# jumping_ring_ariel.net
KiCad netlist of a schematic drawn in EasyEDA
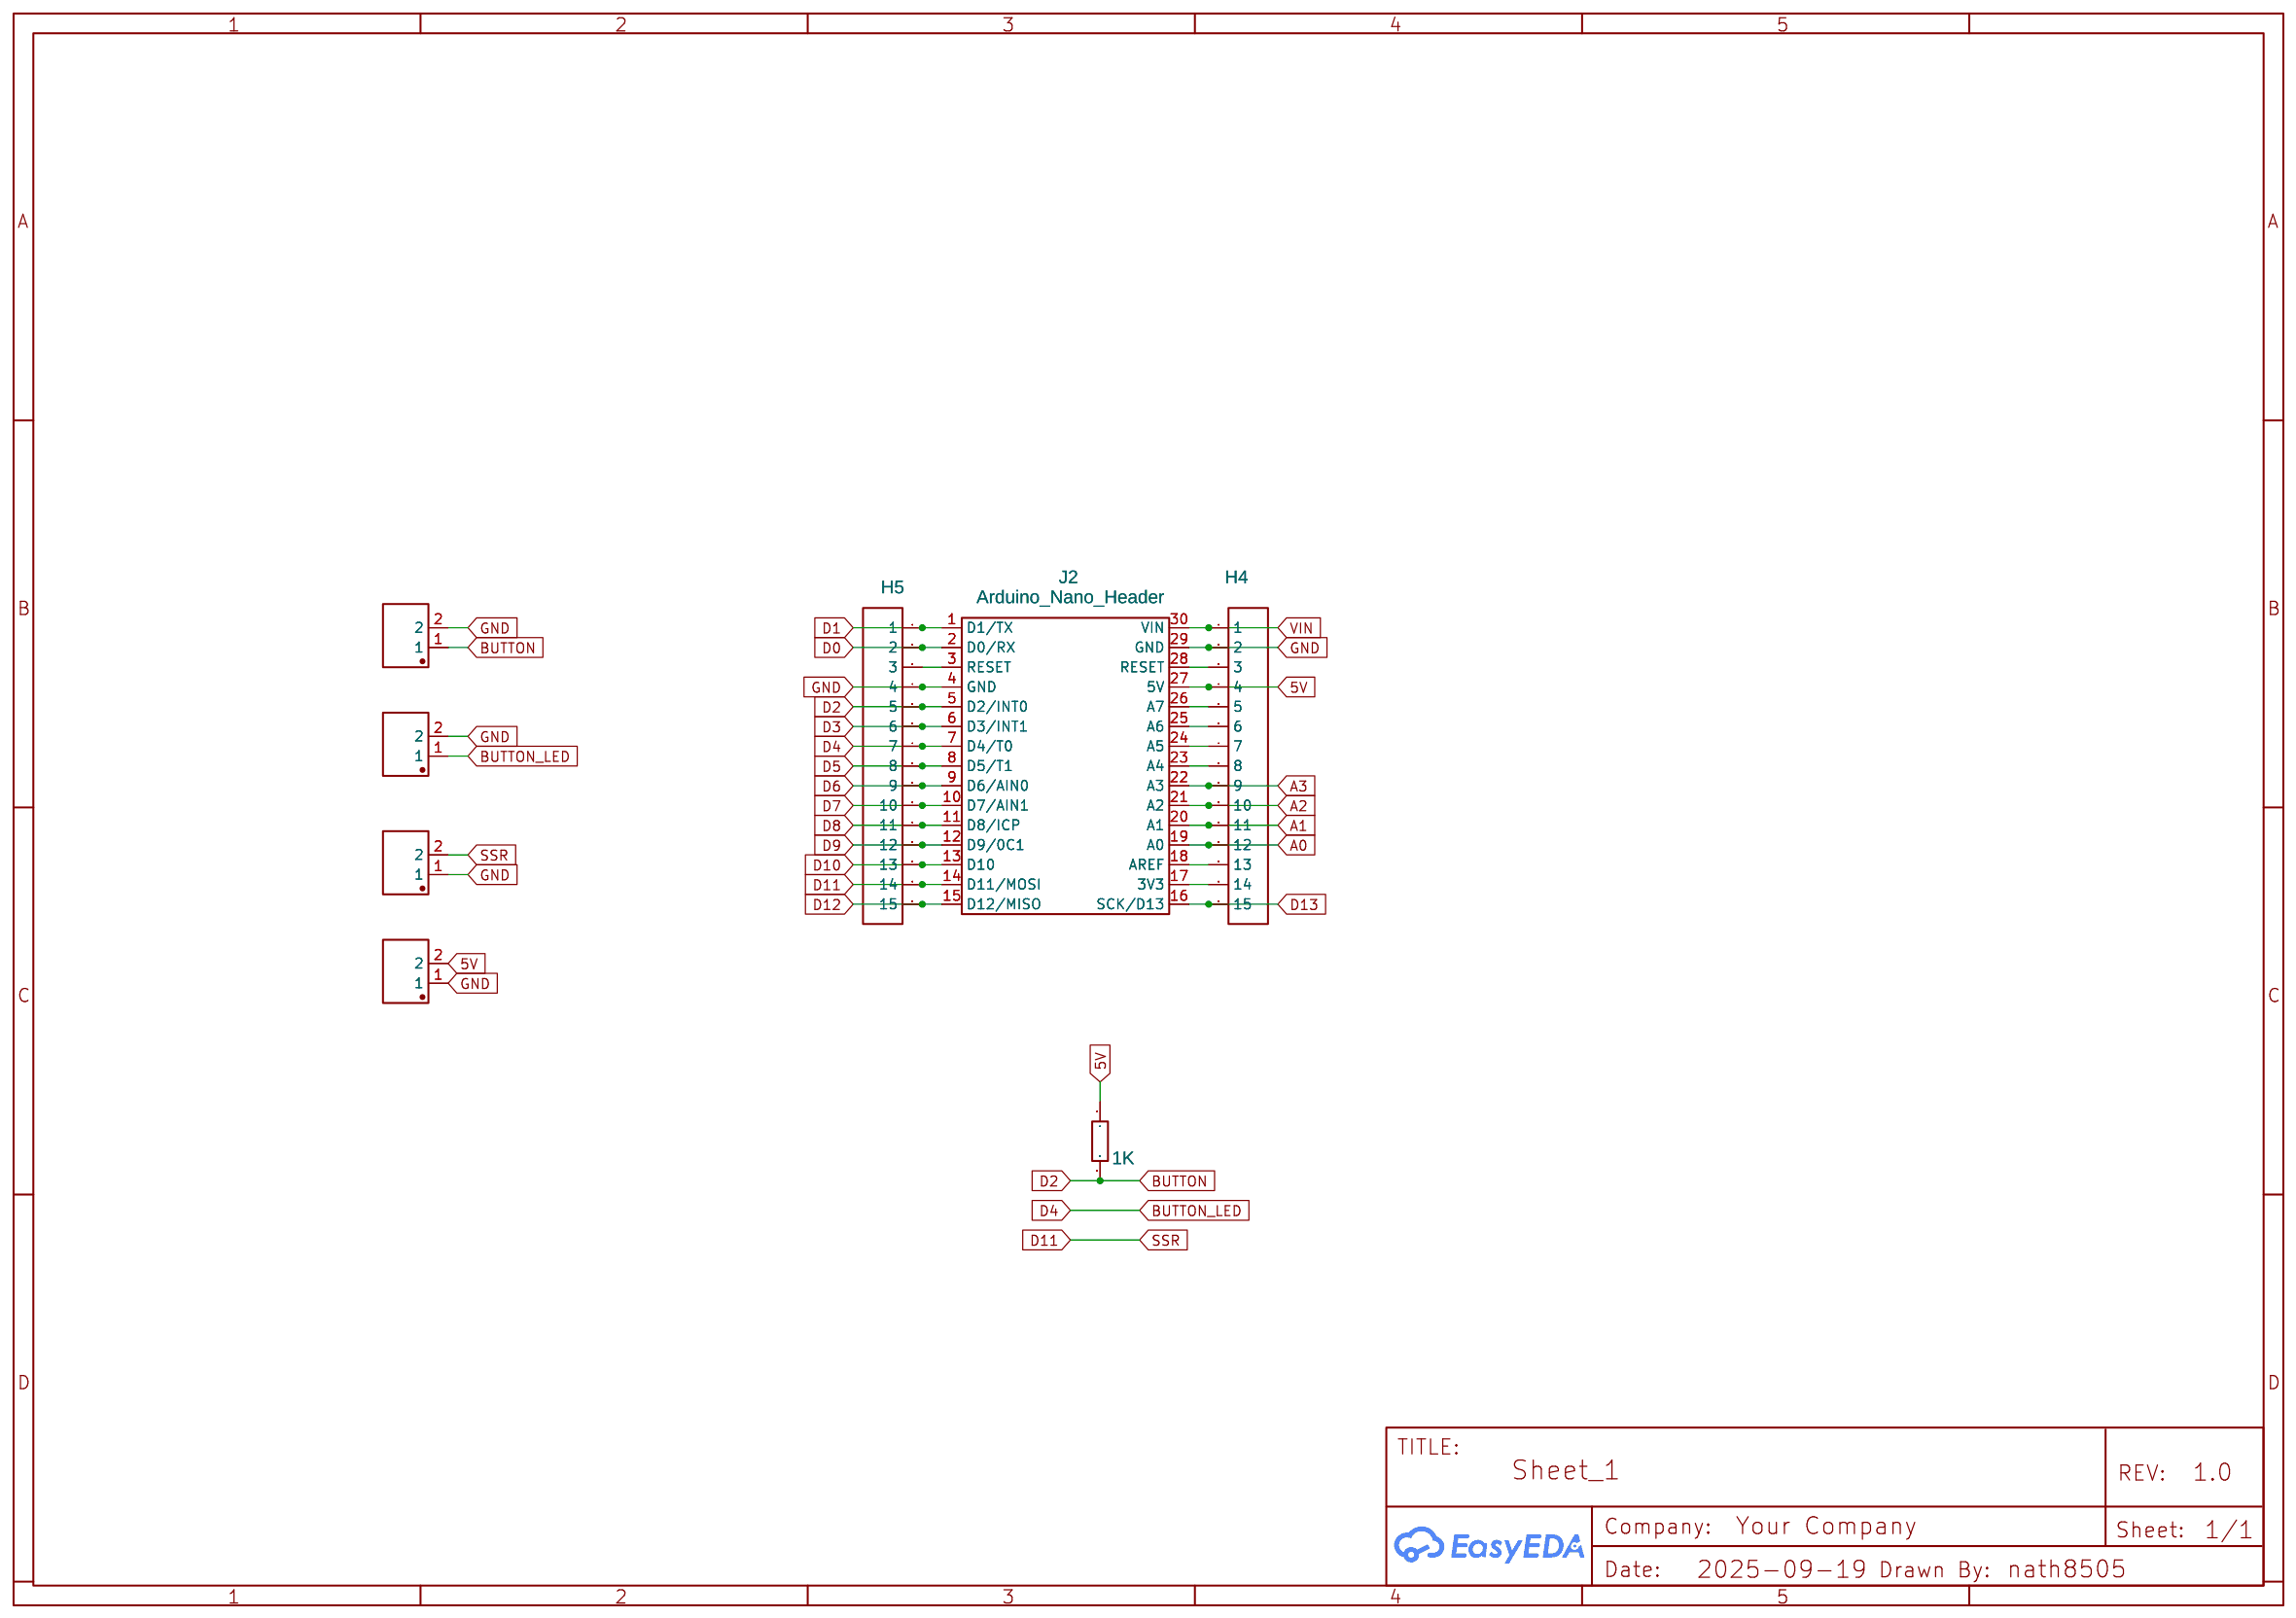
[diagram p0: schematic sheet]

(export (version "E")
  (design (tool "Eeschema 10.0.6"))
  (components
    (comp (ref "D1")
      (value "B-")
      (fields (field (name "Manufacturer Part") "KF2510-2A") (field (name "Manufacturer") "BOOMELE"))
      (libsource (lib "") (part "KF2510-2A"))
    )
    (comp (ref "D2")
      (value "B-")
      (fields (field (name "Manufacturer Part") "KF2510-2A") (field (name "Manufacturer") "BOOMELE"))
      (libsource (lib "") (part "KF2510-2A"))
    )
    (comp (ref "D7")
      (value "B+")
      (fields (field (name "Manufacturer Part") "KF2510-2A") (field (name "Manufacturer") "BOOMELE"))
      (libsource (lib "") (part "KF2510-2A"))
    )
    (comp (ref "D8")
      (value "B-")
      (fields (field (name "Manufacturer Part") "KF2510-2A") (field (name "Manufacturer") "BOOMELE"))
      (libsource (lib "") (part "KF2510-2A"))
    )
    (comp (ref "ERL1")
      (value "1K")
      (fields (field (name "Manufacturer Part") "0603WAF1001T5E") (field (name "Manufacturer") "UniOhm"))
      (libsource (lib "") (part "0603WAF1001T5E"))
    )
    (comp (ref "H4") (value "HDR-F-2.54_1x15") (libsource (lib "") (part "HDR-F-2.54_1x15")))
    (comp (ref "H5") (value "HDR-F-2.54_1x15") (libsource (lib "") (part "HDR-F-2.54_1x15_1")))
    (comp (ref "J2") (value "Arduino_Nano_Header") (libsource (lib "") (part "Arduino_Nano_Header")))
  )
  (nets
    (net (code "1") (name "5V") (class "Default")
      (node (ref "D2") (pin "2") (pinfunction "2_2") (pintype "unspecified"))
      (node (ref "ERL1") (pin "1") (pinfunction "1_1") (pintype "input"))
      (node (ref "H4") (pin "4") (pinfunction "4_4") (pintype "unspecified"))
      (node (ref "J2") (pin "27") (pinfunction "5V_27") (pintype "unspecified"))
    )
    (net (code "2") (name "A0") (class "Default")
      (node (ref "H4") (pin "12") (pinfunction "12_12") (pintype "unspecified"))
      (node (ref "J2") (pin "19") (pinfunction "A0_19") (pintype "unspecified"))
    )
    (net (code "3") (name "A1") (class "Default")
      (node (ref "H4") (pin "11") (pinfunction "11_11") (pintype "unspecified"))
      (node (ref "J2") (pin "20") (pinfunction "A1_20") (pintype "unspecified"))
    )
    (net (code "4") (name "A2") (class "Default")
      (node (ref "H4") (pin "10") (pinfunction "10_10") (pintype "unspecified"))
      (node (ref "J2") (pin "21") (pinfunction "A2_21") (pintype "unspecified"))
    )
    (net (code "5") (name "A3") (class "Default")
      (node (ref "H4") (pin "9") (pinfunction "9_9") (pintype "unspecified"))
      (node (ref "J2") (pin "22") (pinfunction "A3_22") (pintype "unspecified"))
    )
    (net (code "6") (name "BUTTON") (class "Default")
      (node (ref "D7") (pin "1") (pinfunction "1_1") (pintype "unspecified"))
      (node (ref "ERL1") (pin "2") (pinfunction "2_2") (pintype "input"))
      (node (ref "H5") (pin "5") (pinfunction "5_5") (pintype "unspecified"))
      (node (ref "J2") (pin "5") (pinfunction "D2/INT0_5") (pintype "unspecified"))
    )
    (net (code "7") (name "BUTTON_LED") (class "Default")
      (node (ref "D8") (pin "1") (pinfunction "1_1") (pintype "unspecified"))
      (node (ref "H5") (pin "7") (pinfunction "7_7") (pintype "unspecified"))
      (node (ref "J2") (pin "7") (pinfunction "D4/T0_7") (pintype "unspecified"))
    )
    (net (code "8") (name "D0") (class "Default")
      (node (ref "H5") (pin "2") (pinfunction "2_2") (pintype "unspecified"))
      (node (ref "J2") (pin "2") (pinfunction "D0/RX_2") (pintype "unspecified"))
    )
    (net (code "9") (name "D1") (class "Default")
      (node (ref "H5") (pin "1") (pinfunction "1_1") (pintype "unspecified"))
      (node (ref "J2") (pin "1") (pinfunction "D1/TX_1") (pintype "unspecified"))
    )
    (net (code "10") (name "D3") (class "Default")
      (node (ref "H5") (pin "6") (pinfunction "6_6") (pintype "unspecified"))
      (node (ref "J2") (pin "6") (pinfunction "D3/INT1_6") (pintype "unspecified"))
    )
    (net (code "11") (name "D5") (class "Default")
      (node (ref "H5") (pin "8") (pinfunction "8_8") (pintype "unspecified"))
      (node (ref "J2") (pin "8") (pinfunction "D5/T1_8") (pintype "unspecified"))
    )
    (net (code "12") (name "D6") (class "Default")
      (node (ref "H5") (pin "9") (pinfunction "9_9") (pintype "unspecified"))
      (node (ref "J2") (pin "9") (pinfunction "D6/AIN0_9") (pintype "unspecified"))
    )
    (net (code "13") (name "D7") (class "Default")
      (node (ref "H5") (pin "10") (pinfunction "10_10") (pintype "unspecified"))
      (node (ref "J2") (pin "10") (pinfunction "D7/AIN1_10") (pintype "unspecified"))
    )
    (net (code "14") (name "D8") (class "Default")
      (node (ref "H5") (pin "11") (pinfunction "11_11") (pintype "unspecified"))
      (node (ref "J2") (pin "11") (pinfunction "D8/ICP_11") (pintype "unspecified"))
    )
    (net (code "15") (name "D9") (class "Default")
      (node (ref "H5") (pin "12") (pinfunction "12_12") (pintype "unspecified"))
      (node (ref "J2") (pin "12") (pinfunction "D9/0C1_12") (pintype "unspecified"))
    )
    (net (code "16") (name "D10") (class "Default")
      (node (ref "H5") (pin "13") (pinfunction "13_13") (pintype "unspecified"))
      (node (ref "J2") (pin "13") (pinfunction "D10_13") (pintype "unspecified"))
    )
    (net (code "17") (name "D11") (class "Default")
      (node (ref "D1") (pin "2") (pinfunction "2_2") (pintype "unspecified"))
      (node (ref "H5") (pin "14") (pinfunction "14_14") (pintype "unspecified"))
      (node (ref "J2") (pin "14") (pinfunction "D11/MOSI_14") (pintype "unspecified"))
    )
    (net (code "18") (name "D12") (class "Default")
      (node (ref "H5") (pin "15") (pinfunction "15_15") (pintype "unspecified"))
      (node (ref "J2") (pin "15") (pinfunction "D12/MISO_15") (pintype "unspecified"))
    )
    (net (code "19") (name "D13") (class "Default")
      (node (ref "H4") (pin "15") (pinfunction "15_15") (pintype "unspecified"))
      (node (ref "J2") (pin "16") (pinfunction "SCK/D13_16") (pintype "unspecified"))
    )
    (net (code "20") (name "GND") (class "Default")
      (node (ref "D1") (pin "1") (pinfunction "1_1") (pintype "unspecified"))
      (node (ref "D2") (pin "1") (pinfunction "1_1") (pintype "unspecified"))
      (node (ref "D7") (pin "2") (pinfunction "2_2") (pintype "unspecified"))
      (node (ref "D8") (pin "2") (pinfunction "2_2") (pintype "unspecified"))
      (node (ref "H4") (pin "2") (pinfunction "2_2") (pintype "unspecified"))
      (node (ref "H5") (pin "4") (pinfunction "4_4") (pintype "unspecified"))
      (node (ref "J2") (pin "29") (pinfunction "GND_29") (pintype "unspecified"))
      (node (ref "J2") (pin "4") (pinfunction "GND_4") (pintype "unspecified"))
    )
    (net (code "21") (name "Net-(H4-Pad3)") (class "Default")
      (node (ref "H4") (pin "3") (pinfunction "3_3") (pintype "unspecified"))
      (node (ref "J2") (pin "28") (pinfunction "RESET_28") (pintype "unspecified"))
    )
    (net (code "22") (name "Net-(H5-Pad3)") (class "Default")
      (node (ref "H5") (pin "3") (pinfunction "3_3") (pintype "unspecified"))
      (node (ref "J2") (pin "3") (pinfunction "RESET_3") (pintype "unspecified"))
    )
    (net (code "23") (name "Net-(J2-3V3)") (class "Default")
      (node (ref "H4") (pin "14") (pinfunction "14_14") (pintype "unspecified"))
      (node (ref "J2") (pin "17") (pinfunction "3V3_17") (pintype "unspecified"))
    )
    (net (code "24") (name "Net-(J2-A4)") (class "Default")
      (node (ref "H4") (pin "8") (pinfunction "8_8") (pintype "unspecified"))
      (node (ref "J2") (pin "23") (pinfunction "A4_23") (pintype "unspecified"))
    )
    (net (code "25") (name "Net-(J2-A5)") (class "Default")
      (node (ref "H4") (pin "7") (pinfunction "7_7") (pintype "unspecified"))
      (node (ref "J2") (pin "24") (pinfunction "A5_24") (pintype "unspecified"))
    )
    (net (code "26") (name "Net-(J2-A6)") (class "Default")
      (node (ref "H4") (pin "6") (pinfunction "6_6") (pintype "unspecified"))
      (node (ref "J2") (pin "25") (pinfunction "A6_25") (pintype "unspecified"))
    )
    (net (code "27") (name "Net-(J2-A7)") (class "Default")
      (node (ref "H4") (pin "5") (pinfunction "5_5") (pintype "unspecified"))
      (node (ref "J2") (pin "26") (pinfunction "A7_26") (pintype "unspecified"))
    )
    (net (code "28") (name "Net-(J2-AREF)") (class "Default")
      (node (ref "H4") (pin "13") (pinfunction "13_13") (pintype "unspecified"))
      (node (ref "J2") (pin "18") (pinfunction "AREF_18") (pintype "unspecified"))
    )
    (net (code "29") (name "VIN") (class "Default")
      (node (ref "H4") (pin "1") (pinfunction "1_1") (pintype "unspecified"))
      (node (ref "J2") (pin "30") (pinfunction "VIN_30") (pintype "unspecified"))
    )
  )
)
